# External_Debug_Interface.net
KiCad netlist of a schematic drawn in Altium Designer
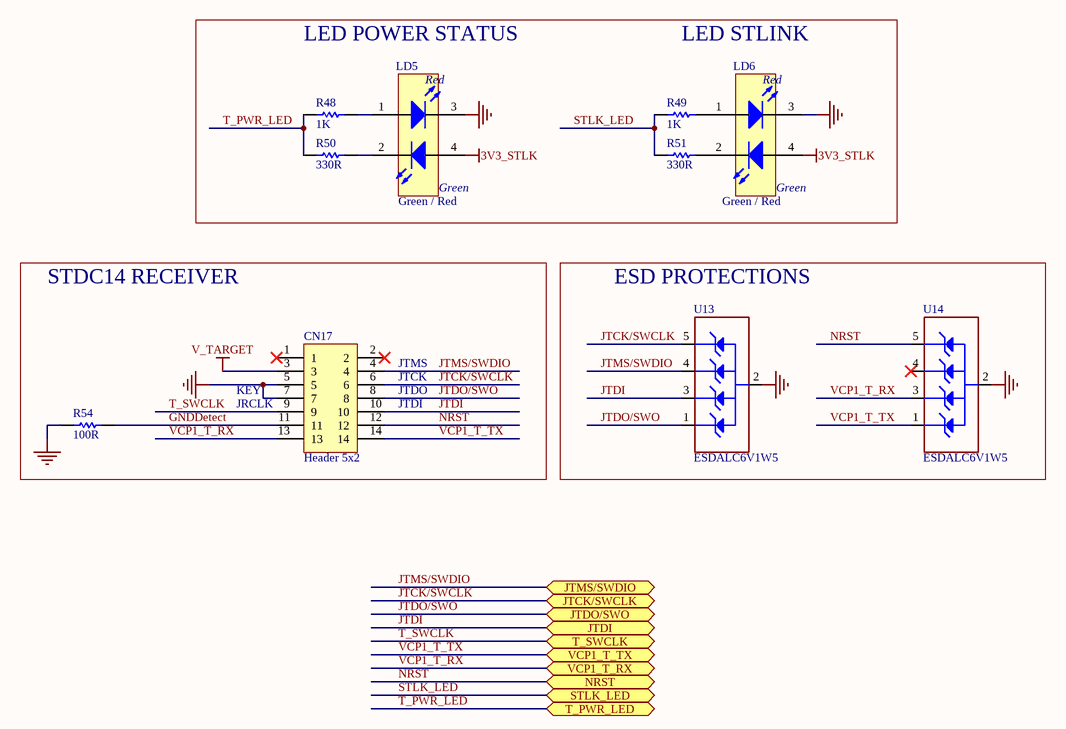
[diagram p0: External_Debug_Interface.SchDoc]

(export (version "E")
  (design (tool "Eeschema 10.0.6"))
  (components
    (comp (ref "CN17")
      (value "Header 5x2")
      (footprint "MCD_PARTS:CON_STDC14_Receiver_MEDIUM_WITH_MIPI10_3D")
      (description "Header, 5x2, 1.27mm, VR, SMD, T=5.97mm/3.05mm")
      (fields (field (name "INTERNAL_PART_NUMBER") "MCD-01226") (field (name "MANUFACTURER") "SAMTEC"))
      (libsource (lib "MCD_PARTS_database") (part "Header 7x2"))
    )
    (comp (ref "LD5")
      (value "Green / Red")
      (footprint "MCD_PARTS:LED_BI-GR_WE-150141SV73110")
      (description "LED Bicolor, Green/Red, 2V, 20mA,  4-PLCC")
      (fields
        (field (name "INTERNAL_PART_NUMBER") "MCD-02631")
        (field (name "MANUFACTURER") "WURTH ELEKTRONIK")
      )
      (libsource (lib "MCD_PARTS_database") (part "LED_BICOLOR"))
    )
    (comp (ref "LD6")
      (value "Green / Red")
      (footprint "MCD_PARTS:LED_BI-GR_WE-150141SV73110")
      (description "LED Bicolor, Green/Red, 2V, 20mA,  4-PLCC")
      (fields
        (field (name "INTERNAL_PART_NUMBER") "MCD-02631")
        (field (name "MANUFACTURER") "WURTH ELEKTRONIK")
      )
      (libsource (lib "MCD_PARTS_database") (part "LED_BICOLOR"))
    )
    (comp (ref "R48")
      (value "1K")
      (footprint "R0402")
      (description "Resistor, 1K, 0402, +/-0.1%, 1/16W, +/-25ppm/°C")
      (fields (field (name "INTERNAL_PART_NUMBER") "MCD-02665") (field (name "MANUFACTURER") "YAGEO"))
      (libsource (lib "MCD_PARTS_database") (part "Resistor"))
    )
    (comp (ref "R49")
      (value "1K")
      (footprint "MCD_PARTS:R0402")
      (description "Resistor, 1K, 0402, +/-0.1%, 1/16W, +/-25ppm/°C")
      (fields (field (name "INTERNAL_PART_NUMBER") "MCD-02665") (field (name "MANUFACTURER") "YAGEO"))
      (libsource (lib "MCD_PARTS_database") (part "Resistor"))
    )
    (comp (ref "R50")
      (value "330R")
      (footprint "MCD_PARTS:R0402")
      (description "Resistor, 330R, 0402, +/-1%, 1/16W")
      (fields (field (name "INTERNAL_PART_NUMBER") "MCD-00062") (field (name "MANUFACTURER") "YAGEO"))
      (libsource (lib "MCD_PARTS_database") (part "Resistor"))
    )
    (comp (ref "R51")
      (value "330R")
      (footprint "MCD_PARTS:R0402")
      (description "Resistor, 330R, 0402, +/-1%, 1/16W")
      (fields (field (name "INTERNAL_PART_NUMBER") "MCD-00062") (field (name "MANUFACTURER") "YAGEO"))
      (libsource (lib "MCD_PARTS_database") (part "Resistor"))
    )
    (comp (ref "R54")
      (value "100R")
      (footprint "R0402")
      (description "Resistor, 100R, 0402, +/- 1%, 1/16W")
      (fields (field (name "INTERNAL_PART_NUMBER") "MCD-00067") (field (name "MANUFACTURER") "YAGEO"))
      (libsource (lib "MCD_PARTS_database") (part "Resistor"))
    )
    (comp (ref "U13")
      (value "ESDALC6V1W5")
      (footprint "MCD_PARTS:ESD_SOT323-5L")
      (description "Dual Transil array for ESD protection")
      (fields (field (name "INTERNAL_PART_NUMBER") "MCD-00136") (field (name "BMS_PART_NUMBER") "9151112"))
      (libsource (lib "MCD_PARTS_database") (part "ESDALC6V1W5"))
    )
    (comp (ref "U14")
      (value "ESDALC6V1W5")
      (footprint "MCD_PARTS:ESD_SOT323-5L")
      (description "Dual Transil array for ESD protection")
      (fields (field (name "INTERNAL_PART_NUMBER") "MCD-00136") (field (name "BMS_PART_NUMBER") "9151112"))
      (libsource (lib "MCD_PARTS_database") (part "ESDALC6V1W5"))
    )
  )
  (nets
    (net (code "1") (name "/GNDDetect") (class "Default")
      (node (ref "CN17") (pin "11") (pinfunction "11_11") (pintype "passive"))
      (node (ref "R54") (pin "2") (pinfunction "2_2") (pintype "passive"))
    )
    (net (code "2") (name "/JTCK{slash}SWCLK") (class "Default")
      (node (ref "CN17") (pin "6") (pinfunction "6_6") (pintype "passive"))
      (node (ref "U13") (pin "5") (pinfunction "IO4_5") (pintype "passive"))
    )
    (net (code "3") (name "/JTDI") (class "Default")
      (node (ref "CN17") (pin "10") (pinfunction "10_10") (pintype "passive"))
      (node (ref "U13") (pin "3") (pinfunction "IO2_3") (pintype "passive"))
    )
    (net (code "4") (name "/JTDO{slash}SWO") (class "Default")
      (node (ref "CN17") (pin "8") (pinfunction "8_8") (pintype "passive"))
      (node (ref "U13") (pin "1") (pinfunction "IO1_1") (pintype "passive"))
    )
    (net (code "5") (name "/JTMS{slash}SWDIO") (class "Default")
      (node (ref "CN17") (pin "4") (pinfunction "4_4") (pintype "passive"))
      (node (ref "U13") (pin "4") (pinfunction "IO3_4") (pintype "passive"))
    )
    (net (code "6") (name "/NRST") (class "Default")
      (node (ref "CN17") (pin "12") (pinfunction "12_12") (pintype "passive"))
      (node (ref "U14") (pin "5") (pinfunction "IO4_5") (pintype "passive"))
    )
    (net (code "7") (name "/STLK_LED") (class "Default")
      (node (ref "R49") (pin "2") (pinfunction "2_2") (pintype "passive"))
      (node (ref "R51") (pin "1") (pinfunction "1_1") (pintype "passive"))
    )
    (net (code "8") (name "/T_PWR_LED") (class "Default")
      (node (ref "R48") (pin "2") (pinfunction "2_2") (pintype "passive"))
      (node (ref "R50") (pin "2") (pinfunction "2_2") (pintype "passive"))
    )
    (net (code "9") (name "/T_SWCLK") (class "Default")
      (node (ref "CN17") (pin "9") (pinfunction "9_9") (pintype "passive"))
    )
    (net (code "10") (name "/VCP1_T_RX") (class "Default")
      (node (ref "CN17") (pin "13") (pinfunction "13_13") (pintype "passive"))
      (node (ref "U14") (pin "3") (pinfunction "IO2_3") (pintype "passive"))
    )
    (net (code "11") (name "/VCP1_T_TX") (class "Default")
      (node (ref "CN17") (pin "14") (pinfunction "14_14") (pintype "passive"))
      (node (ref "U14") (pin "1") (pinfunction "IO1_1") (pintype "passive"))
    )
    (net (code "12") (name "3V3_STLK") (class "Default")
      (node (ref "LD5") (pin "4") (pinfunction "Green_anode_4") (pintype "passive"))
      (node (ref "LD6") (pin "4") (pinfunction "Green_anode_4") (pintype "passive"))
    )
    (net (code "13") (name "GND") (class "Default")
      (node (ref "CN17") (pin "5") (pinfunction "5_5") (pintype "passive"))
      (node (ref "CN17") (pin "7") (pinfunction "7_7") (pintype "passive"))
      (node (ref "LD5") (pin "3") (pinfunction "RED_cathode_3") (pintype "passive"))
      (node (ref "LD6") (pin "3") (pinfunction "RED_cathode_3") (pintype "passive"))
      (node (ref "R54") (pin "1") (pinfunction "1_1") (pintype "passive"))
      (node (ref "U13") (pin "2") (pinfunction "GND_2") (pintype "passive"))
      (node (ref "U14") (pin "2") (pinfunction "GND_2") (pintype "passive"))
    )
    (net (code "14") (name "Net-(LD5-Green_cathode)") (class "Default")
      (node (ref "LD5") (pin "2") (pinfunction "Green_cathode_2") (pintype "passive"))
      (node (ref "R50") (pin "1") (pinfunction "1_1") (pintype "passive"))
    )
    (net (code "15") (name "Net-(LD5-Red_anode)") (class "Default")
      (node (ref "LD5") (pin "1") (pinfunction "Red_anode_1") (pintype "passive"))
      (node (ref "R48") (pin "1") (pinfunction "1_1") (pintype "passive"))
    )
    (net (code "16") (name "Net-(LD6-Green_cathode)") (class "Default")
      (node (ref "LD6") (pin "2") (pinfunction "Green_cathode_2") (pintype "passive"))
      (node (ref "R51") (pin "2") (pinfunction "2_2") (pintype "passive"))
    )
    (net (code "17") (name "Net-(LD6-Red_anode)") (class "Default")
      (node (ref "LD6") (pin "1") (pinfunction "Red_anode_1") (pintype "passive"))
      (node (ref "R49") (pin "1") (pinfunction "1_1") (pintype "passive"))
    )
    (net (code "18") (name "V_TARGET") (class "Default")
      (node (ref "CN17") (pin "3") (pinfunction "3_3") (pintype "passive"))
    )
    (net (code "19") (name "unconnected-(CN17-Pad1)") (class "Default")
      (node (ref "CN17") (pin "1") (pinfunction "1_1") (pintype "passive+no_connect"))
    )
    (net (code "20") (name "unconnected-(CN17-Pad2)") (class "Default")
      (node (ref "CN17") (pin "2") (pinfunction "2_2") (pintype "passive+no_connect"))
    )
    (net (code "21") (name "unconnected-(U14-IO3-Pad4)") (class "Default")
      (node (ref "U14") (pin "4") (pinfunction "IO3_4") (pintype "passive+no_connect"))
    )
  )
)
